# 06_IN_OUT_SENSOR.net
KiCad netlist of a schematic drawn in Altium Designer
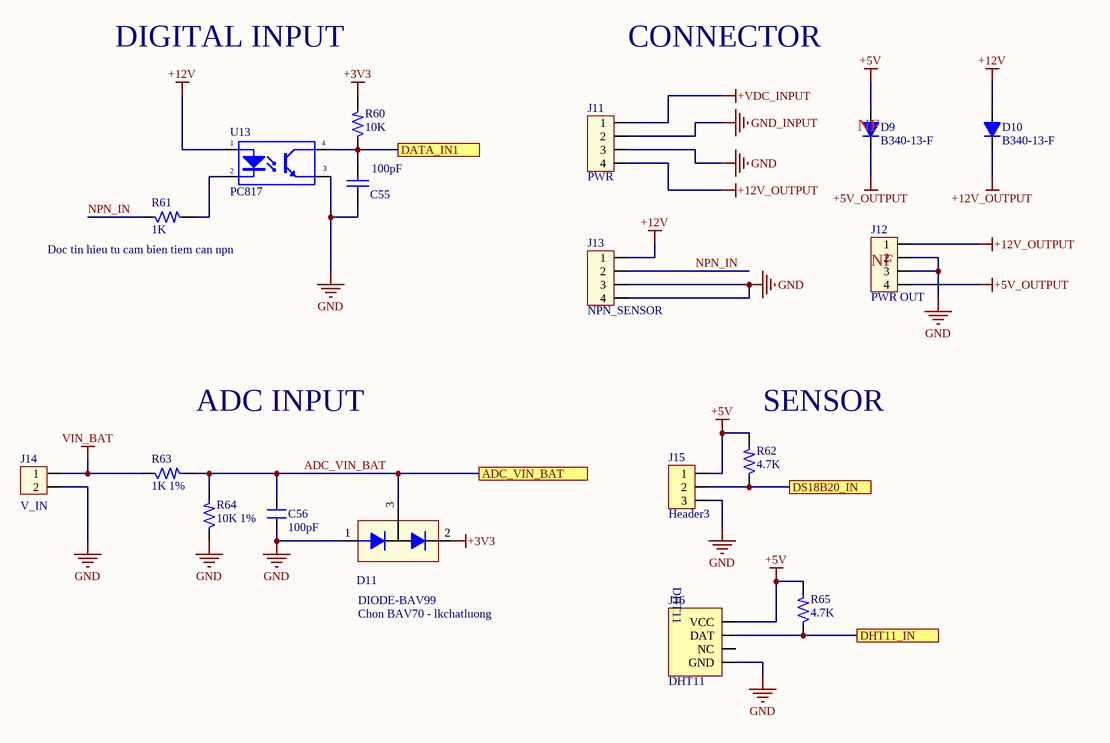
[diagram p0: [06] IN_OUT_SENSOR.SchDoc]

(export (version "E")
  (design (tool "Eeschema 10.0.6"))
  (components
    (comp (ref "C55")
      (value "100pF")
      (footprint "CAP_0805")
      (description "Capacitor")
      (fields (field (name "PUBLISHER") "Altium Limited"))
      (libsource (lib "My Library") (part "CapSMD"))
    )
    (comp (ref "C56")
      (value "100pF")
      (footprint "CAP_0805")
      (description "Cap SMD")
      (libsource (lib "khapham") (part "CM"))
    )
    (comp (ref "D9")
      (value "B340-13-F")
      (footprint "DO-214AB SMA")
      (description "Diode 1A")
      (libsource (lib "GPS_Traking_V1_1") (part "D1A"))
    )
    (comp (ref "D10")
      (value "B340-13-F")
      (footprint "DO-214AB SMA")
      (description "Diode 1A")
      (libsource (lib "GPS_Traking_V1_1") (part "D1A"))
    )
    (comp (ref "D11")
      (value "DIODE-BAV99")
      (footprint "SOT23")
      (description "ZENER, SOT23,")
      (fields
        (field (name "MANUFACTURER") "ON Semiconductor / Fairchild")
        (field (name "MANUFACTURER PART NUMBER") "BAV99")
        (field (name ".CREATOR") "LeKhaLinh")
        (field (name ".CHECKPCB") "LeKhaLinh")
        (field (name ".CHECKSCH") "LeKhaLinh")
      )
      (libsource (lib "GPS_Traking_V1_1") (part "DIODE-BAV99"))
    )
    (comp (ref "J11")
      (value "PWR")
      (footprint "Hed4V_3.96")
      (description "Header 4 (Green)")
      (libsource (lib "GPS_Traking_V1_1") (part "Hed4"))
    )
    (comp (ref "J12")
      (value "PWR OUT")
      (footprint "CON_2.54mm_4")
      (description "Connector 4")
      (libsource (lib "GPS_Traking_V1_1") (part "Con4"))
    )
    (comp (ref "J13")
      (value "NPN_SENSOR")
      (footprint "CON_2.54mm_4")
      (description "Connector 4")
      (libsource (lib "GPS_Traking_V1_1") (part "Con4"))
    )
    (comp (ref "J14")
      (value "V_IN")
      (footprint "CON_2.54mm_2")
      (description "Connector 2")
      (libsource (lib "khapham") (part "Con2"))
    )
    (comp (ref "J15")
      (value "Header3")
      (footprint "Header3")
      (description "Header IDC, 3 x 1 Pin Vertical 2.54mm Pitch (Non-Boxed, Male)")
      (fields
        (field (name "MANUFACTURER") "Würth Elektronik eiSos GmbH")
        (field (name "PARTNO") "613002143121")
        (field (name "CREATED BY") "Karrer Zheng")
      )
      (libsource (lib "My Library") (part "Header3"))
    )
    (comp (ref "J16")
      (value "DHT11")
      (footprint "DHT11")
      (fields
        (field (name "MANUFACTURER") "Würth Elektronik eiSos GmbH")
        (field (name "PARTNO") "613004143121")
        (field (name "CREATED BY") "Karrer Zheng")
      )
      (libsource (lib "My Library") (part "DHT11"))
    )
    (comp (ref "R60")
      (value "10K")
      (footprint "RES-SMD-0805")
      (description "Resistor SMD")
      (libsource (lib "khapham") (part "RM"))
    )
    (comp (ref "R61")
      (value "1K")
      (footprint "RES-SMD-0805")
      (description "Resistor SMD")
      (libsource (lib "khapham") (part "RM"))
    )
    (comp (ref "R62")
      (value "4.7K")
      (footprint "RES-SMD-0805")
      (description "Resistor SMD")
      (libsource (lib "khapham") (part "RM"))
    )
    (comp (ref "R63")
      (value "1K 1%")
      (footprint "RES-SMD-0805")
      (description "Resistor SMD")
      (libsource (lib "khapham") (part "RM"))
    )
    (comp (ref "R64")
      (value "10K 1%")
      (footprint "RES-SMD-0805")
      (description "Resistor SMD")
      (libsource (lib "khapham") (part "RM"))
    )
    (comp (ref "R65")
      (value "4.7K")
      (footprint "RES-SMD-0805")
      (description "Resistor SMD")
      (libsource (lib "khapham") (part "RM"))
    )
    (comp (ref "U13")
      (value "PC817")
      (footprint "DIP4/W0.3")
      (description "Single Opto")
      (libsource (lib "GPS_Traking_V1_1") (part "PC817"))
    )
  )
  (nets
    (net (code "1") (name "+3V3") (class "Default")
      (node (ref "D11") (pin "2") (pinfunction "2_2") (pintype "passive"))
      (node (ref "R60") (pin "2") (pinfunction "2_2") (pintype "passive"))
    )
    (net (code "2") (name "+5V") (class "Default")
      (node (ref "D9") (pin "1") (pinfunction "A_1") (pintype "passive"))
      (node (ref "J15") (pin "1") (pinfunction "1_1") (pintype "passive"))
      (node (ref "J16") (pin "1") (pinfunction "VCC_1") (pintype "passive"))
      (node (ref "R62") (pin "2") (pinfunction "2_2") (pintype "passive"))
      (node (ref "R65") (pin "2") (pinfunction "2_2") (pintype "passive"))
    )
    (net (code "3") (name "+5V_OUTPUT") (class "Default")
      (node (ref "D9") (pin "2") (pinfunction "K_2") (pintype "passive"))
      (node (ref "J12") (pin "4") (pinfunction "4_4") (pintype "passive"))
    )
    (net (code "4") (name "+12V") (class "Default")
      (node (ref "D10") (pin "1") (pinfunction "A_1") (pintype "passive"))
      (node (ref "J13") (pin "1") (pinfunction "1_1") (pintype "passive"))
      (node (ref "U13") (pin "1") (pinfunction "A_1") (pintype "passive"))
    )
    (net (code "5") (name "+12V_OUTPUT") (class "Default")
      (node (ref "D10") (pin "2") (pinfunction "K_2") (pintype "passive"))
      (node (ref "J11") (pin "4") (pinfunction "4_4") (pintype "passive"))
      (node (ref "J12") (pin "1") (pinfunction "1_1") (pintype "passive"))
    )
    (net (code "6") (name "+VDC_INPUT") (class "Default")
      (node (ref "J11") (pin "1") (pinfunction "1_1") (pintype "passive"))
    )
    (net (code "7") (name "/ADC_VIN_BAT") (class "Default")
      (node (ref "C56") (pin "2") (pinfunction "2_2") (pintype "passive"))
      (node (ref "D11") (pin "3") (pinfunction "3_3") (pintype "passive"))
      (node (ref "R63") (pin "2") (pinfunction "2_2") (pintype "passive"))
      (node (ref "R64") (pin "2") (pinfunction "2_2") (pintype "passive"))
    )
    (net (code "8") (name "/DATA_IN1") (class "Default")
      (node (ref "C55") (pin "1") (pinfunction "1_1") (pintype "passive"))
      (node (ref "R60") (pin "1") (pinfunction "1_1") (pintype "passive"))
      (node (ref "U13") (pin "4") (pinfunction "C_4") (pintype "passive"))
    )
    (net (code "9") (name "/DHT11_IN") (class "Default")
      (node (ref "J16") (pin "2") (pinfunction "DAT_2") (pintype "passive"))
      (node (ref "R65") (pin "1") (pinfunction "1_1") (pintype "passive"))
    )
    (net (code "10") (name "/DS18B20_IN") (class "Default")
      (node (ref "J15") (pin "2") (pinfunction "2_2") (pintype "passive"))
      (node (ref "R62") (pin "1") (pinfunction "1_1") (pintype "passive"))
    )
    (net (code "11") (name "/NPN_IN") (class "Default")
      (node (ref "J13") (pin "2") (pinfunction "2_2") (pintype "passive"))
      (node (ref "R61") (pin "1") (pinfunction "1_1") (pintype "passive"))
    )
    (net (code "12") (name "GND") (class "Default")
      (node (ref "C55") (pin "2") (pinfunction "2_2") (pintype "passive"))
      (node (ref "C56") (pin "1") (pinfunction "1_1") (pintype "passive"))
      (node (ref "D11") (pin "1") (pinfunction "1_1") (pintype "passive"))
      (node (ref "J11") (pin "3") (pinfunction "3_3") (pintype "passive"))
      (node (ref "J12") (pin "2") (pinfunction "2_2") (pintype "passive"))
      (node (ref "J12") (pin "3") (pinfunction "3_3") (pintype "passive"))
      (node (ref "J13") (pin "3") (pinfunction "3_3") (pintype "passive"))
      (node (ref "J13") (pin "4") (pinfunction "4_4") (pintype "passive"))
      (node (ref "J14") (pin "2") (pinfunction "2_2") (pintype "passive"))
      (node (ref "J15") (pin "3") (pinfunction "3_3") (pintype "passive"))
      (node (ref "J16") (pin "4") (pinfunction "GND_4") (pintype "passive"))
      (node (ref "R64") (pin "1") (pinfunction "1_1") (pintype "passive"))
      (node (ref "U13") (pin "3") (pinfunction "E_3") (pintype "passive"))
    )
    (net (code "13") (name "GND_INPUT") (class "Default")
      (node (ref "J11") (pin "2") (pinfunction "2_2") (pintype "passive"))
    )
    (net (code "14") (name "Net-(U13-K)") (class "Default")
      (node (ref "R61") (pin "2") (pinfunction "2_2") (pintype "passive"))
      (node (ref "U13") (pin "2") (pinfunction "K_2") (pintype "passive"))
    )
    (net (code "15") (name "VIN_BAT") (class "Default")
      (node (ref "J14") (pin "1") (pinfunction "1_1") (pintype "passive"))
      (node (ref "R63") (pin "1") (pinfunction "1_1") (pintype "passive"))
    )
    (net (code "16") (name "unconnected-(J16-NC-Pad3)") (class "Default")
      (node (ref "J16") (pin "3") (pinfunction "NC_3") (pintype "passive"))
    )
  )
)
